# 685623_177_3.net
KiCad netlist of a schematic drawn in Altium Designer
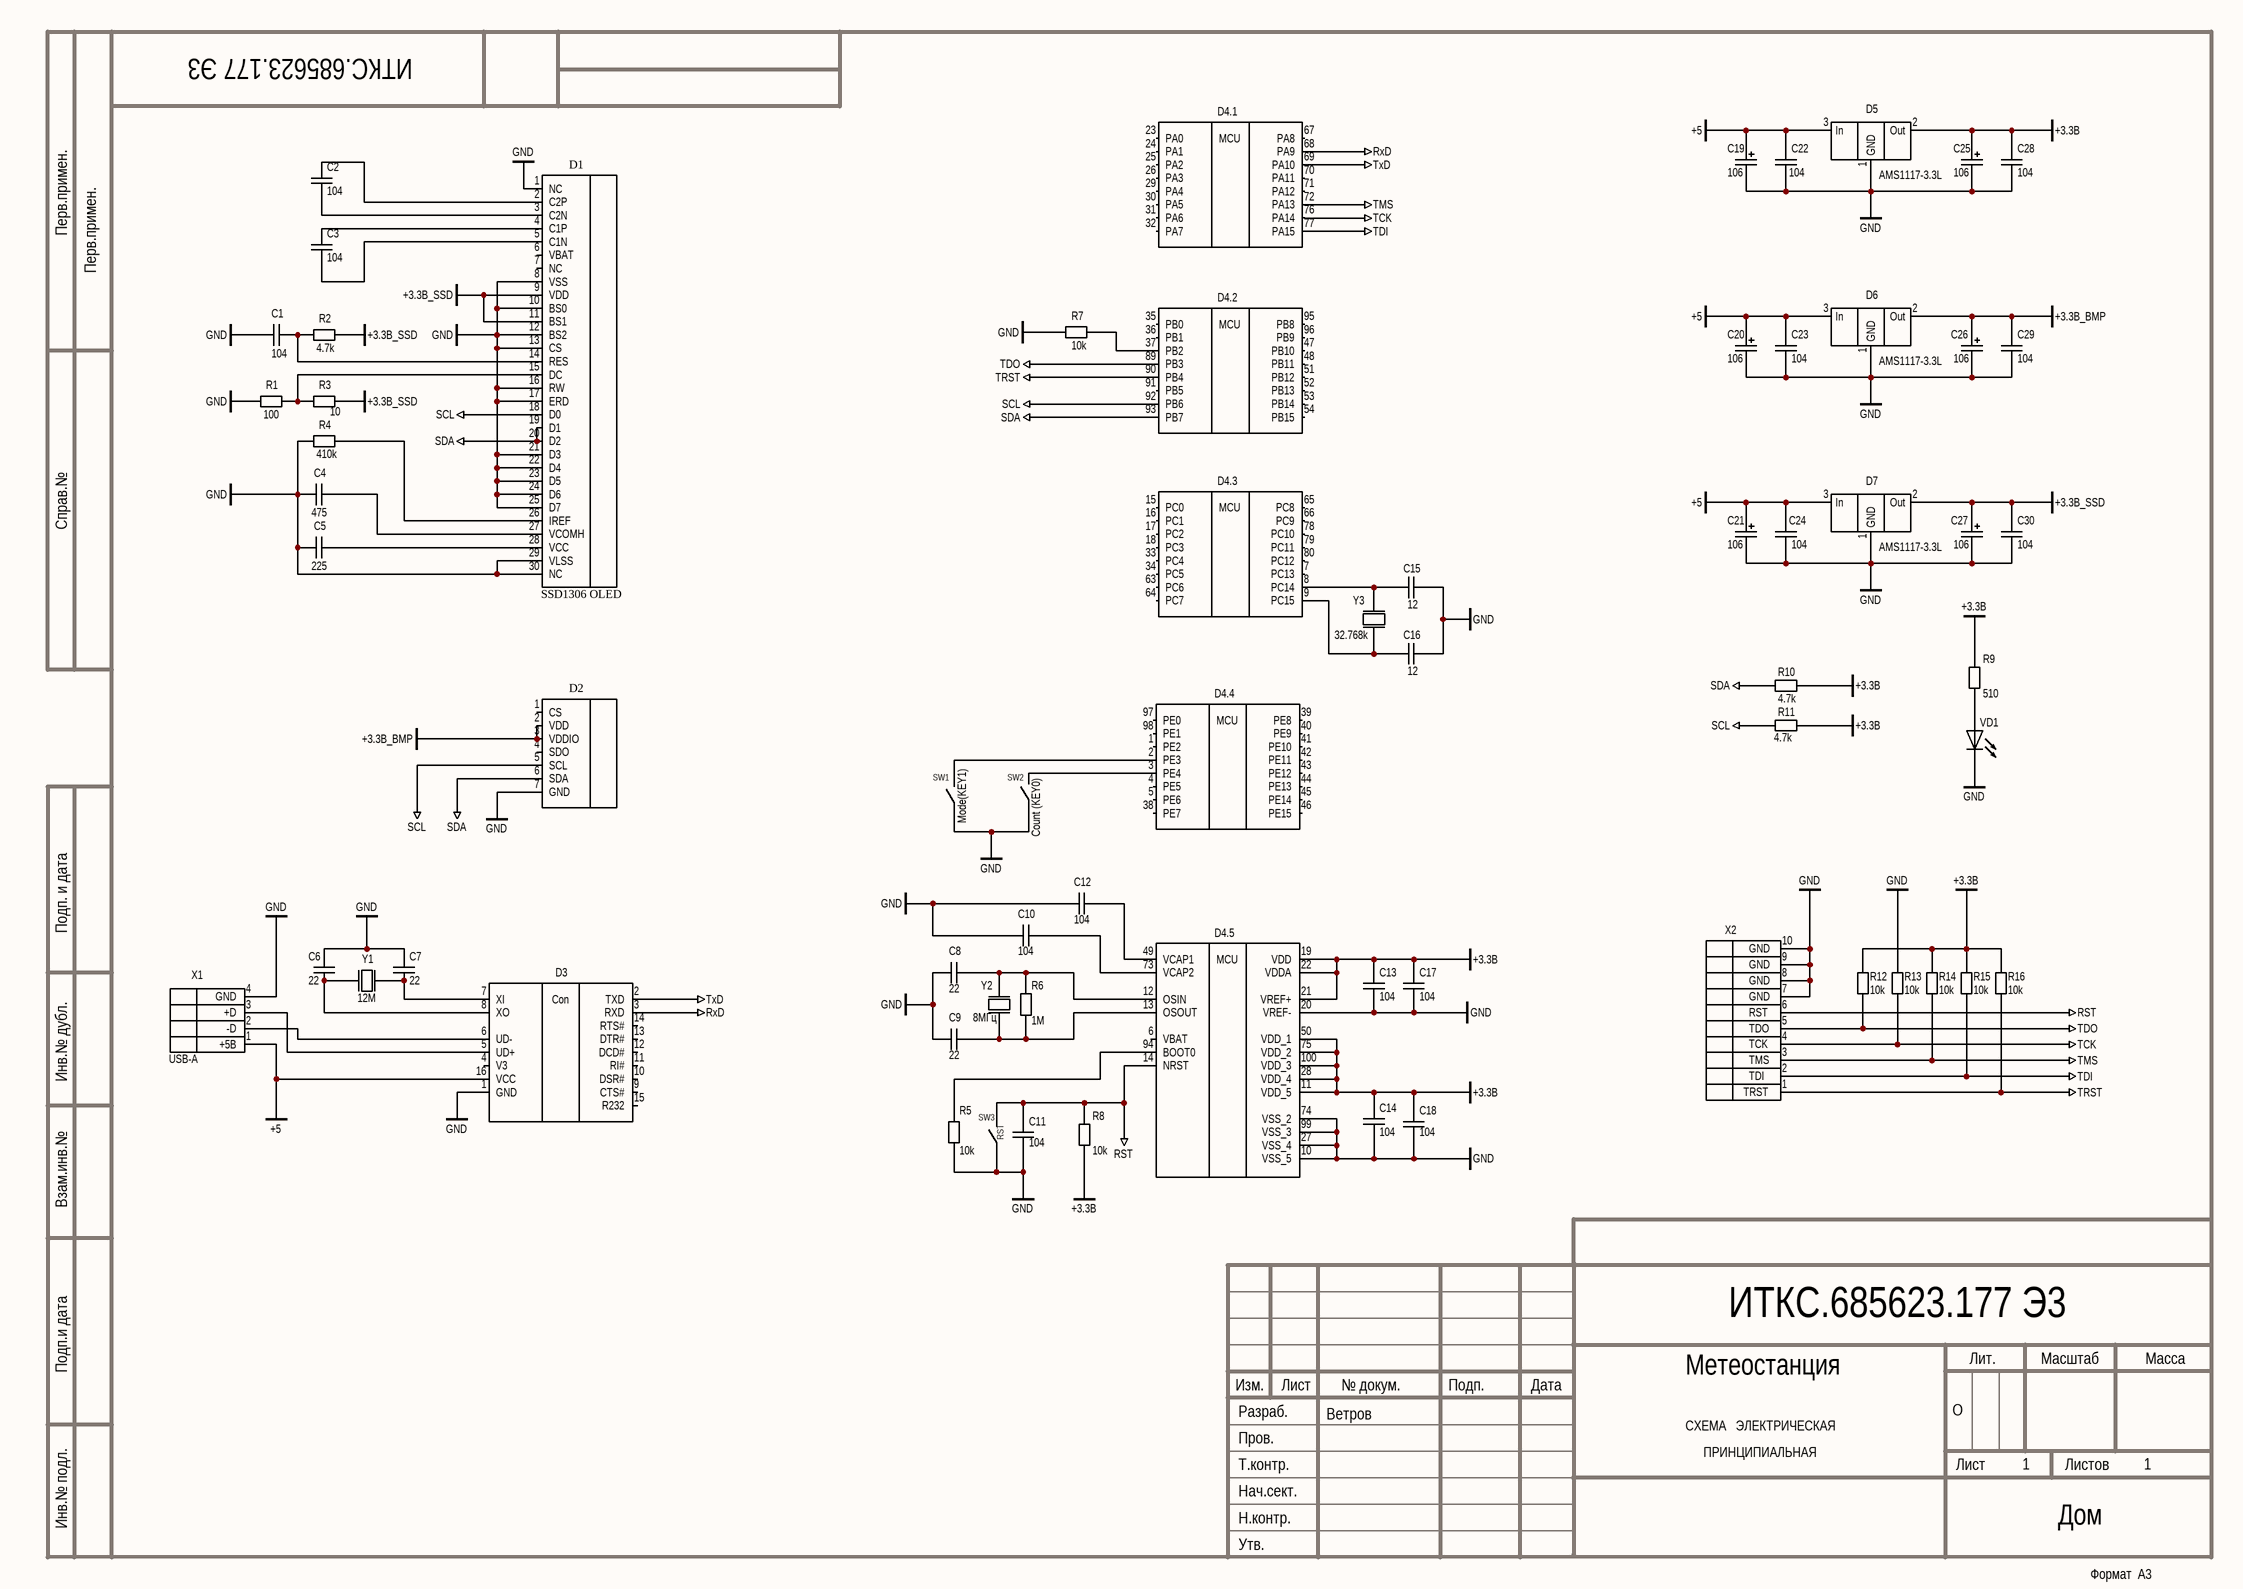
[diagram p0: ИТКС.685623.177 Э3.SchDoc]

(export (version "E")
  (design (tool "Eeschema 10.0.6"))
  (components
    (comp (ref "C1") (value "104") (footprint "0603") (libsource (lib "MainLib") (part "C")))
    (comp (ref "C2") (value "104") (footprint "0603") (libsource (lib "MainLib") (part "C")))
    (comp (ref "C3") (value "104") (footprint "0603") (libsource (lib "MainLib") (part "C")))
    (comp (ref "C4") (value "475") (footprint "0603") (libsource (lib "MainLib") (part "C")))
    (comp (ref "C5") (value "225") (footprint "0603") (libsource (lib "MainLib") (part "C")))
    (comp (ref "C6") (value "22") (footprint "0603") (libsource (lib "MainLib") (part "C")))
    (comp (ref "C7") (value "22") (footprint "0603") (libsource (lib "MainLib") (part "C")))
    (comp (ref "C8") (value "22") (footprint "0603") (libsource (lib "MainLib") (part "C")))
    (comp (ref "C9") (value "22") (footprint "0603") (libsource (lib "MainLib") (part "C")))
    (comp (ref "C10") (value "104") (footprint "0603") (libsource (lib "MainLib") (part "C")))
    (comp (ref "C11") (value "104") (footprint "0603") (libsource (lib "MainLib") (part "C")))
    (comp (ref "C12") (value "104") (footprint "0603") (libsource (lib "MainLib") (part "C")))
    (comp (ref "C13") (value "104") (footprint "0603") (libsource (lib "MainLib") (part "C")))
    (comp (ref "C14") (value "104") (footprint "0603") (libsource (lib "MainLib") (part "C")))
    (comp (ref "C15") (value "12") (footprint "0603") (libsource (lib "MainLib") (part "C")))
    (comp (ref "C16") (value "12") (footprint "0603") (libsource (lib "MainLib") (part "C")))
    (comp (ref "C17") (value "104") (footprint "0603") (libsource (lib "MainLib") (part "C")))
    (comp (ref "C18") (value "104") (footprint "0603") (libsource (lib "MainLib") (part "C")))
    (comp (ref "C19")
      (value "106")
      (footprint "EIA_6032–28")
      (description "TECAP EIA 6032–28")
      (libsource (lib "MainLib") (part "C+ TECAP"))
    )
    (comp (ref "C20")
      (value "106")
      (footprint "EIA_6032–28")
      (description "TECAP EIA 6032–28")
      (libsource (lib "MainLib") (part "C+ TECAP"))
    )
    (comp (ref "C21")
      (value "106")
      (footprint "EIA_6032–28")
      (description "TECAP EIA 6032–28")
      (libsource (lib "MainLib") (part "C+ TECAP"))
    )
    (comp (ref "C22") (value "104") (footprint "0603") (libsource (lib "MainLib") (part "C")))
    (comp (ref "C23") (value "104") (footprint "0603") (libsource (lib "MainLib") (part "C")))
    (comp (ref "C24") (value "104") (footprint "0603") (libsource (lib "MainLib") (part "C")))
    (comp (ref "C25")
      (value "106")
      (footprint "EIA_6032–28")
      (description "TECAP EIA 6032–28")
      (libsource (lib "MainLib") (part "C+ TECAP"))
    )
    (comp (ref "C26")
      (value "106")
      (footprint "EIA_6032–28")
      (description "TECAP EIA 6032–28")
      (libsource (lib "MainLib") (part "C+ TECAP"))
    )
    (comp (ref "C27")
      (value "106")
      (footprint "EIA_6032–28")
      (description "TECAP EIA 6032–28")
      (libsource (lib "MainLib") (part "C+ TECAP"))
    )
    (comp (ref "C28") (value "104") (footprint "0603") (libsource (lib "MainLib") (part "C")))
    (comp (ref "C29") (value "104") (footprint "0603") (libsource (lib "MainLib") (part "C")))
    (comp (ref "C30") (value "104") (footprint "0603") (libsource (lib "MainLib") (part "C")))
    (comp (ref "D1")
      (value "SSD1306 OLED")
      (footprint "SSD1306")
      (libsource (lib "MainLib") (part "SSD1306 OLED"))
    )
    (comp (ref "D2") (value "BMP180") (footprint "BMP180") (libsource (lib "MainLib") (part "BMP180")))
    (comp (ref "D3") (value "CH340G") (footprint "SOP16") (libsource (lib "MainLib") (part "CH340G")))
    (comp (ref "D4")
      (value "STM32F407VE")
      (footprint "LQFP100")
      (description "ARM3")
      (libsource (lib "MainLib") (part "STM32F407VE"))
    )
    (comp (ref "D5")
      (value "AMS1117-3.3L")
      (footprint "SOT223-4N")
      (libsource (lib "MainLib") (part "AMS1117-3.3L"))
    )
    (comp (ref "D6")
      (value "AMS1117-3.3L")
      (footprint "SOT223-4N")
      (libsource (lib "MainLib") (part "AMS1117-3.3L"))
    )
    (comp (ref "D7")
      (value "AMS1117-3.3L")
      (footprint "SOT223-4N")
      (libsource (lib "MainLib") (part "AMS1117-3.3L"))
    )
    (comp (ref "R1") (value "100") (footprint "0603") (libsource (lib "MainLib") (part "R")))
    (comp (ref "R2") (value "4.7k") (footprint "0603") (libsource (lib "MainLib") (part "R")))
    (comp (ref "R3") (value "10") (footprint "0603") (libsource (lib "MainLib") (part "R")))
    (comp (ref "R4") (value "410k") (footprint "0603") (libsource (lib "MainLib") (part "R")))
    (comp (ref "R5") (value "10k") (footprint "0603") (libsource (lib "MainLib") (part "R")))
    (comp (ref "R6") (value "1M") (footprint "0603") (libsource (lib "MainLib") (part "R")))
    (comp (ref "R7") (value "10k") (footprint "0603") (libsource (lib "MainLib") (part "R")))
    (comp (ref "R8") (value "10k") (footprint "0603") (libsource (lib "MainLib") (part "R")))
    (comp (ref "R9") (value "510") (footprint "0603") (libsource (lib "MainLib") (part "R")))
    (comp (ref "R10") (value "4.7k") (footprint "0603") (libsource (lib "MainLib") (part "R")))
    (comp (ref "R11") (value "4.7k") (footprint "0603") (libsource (lib "MainLib") (part "R")))
    (comp (ref "R12") (value "10k") (footprint "0603") (libsource (lib "MainLib") (part "R")))
    (comp (ref "R13") (value "10k") (footprint "0603") (libsource (lib "MainLib") (part "R")))
    (comp (ref "R14") (value "10k") (footprint "0603") (libsource (lib "MainLib") (part "R")))
    (comp (ref "R15") (value "10k") (footprint "0603") (libsource (lib "MainLib") (part "R")))
    (comp (ref "R16") (value "10k") (footprint "0603") (libsource (lib "MainLib") (part "R")))
    (comp (ref "SW1") (value "Mode(KEY1)") (footprint "0603") (libsource (lib "MainLib") (part "Button")))
    (comp (ref "SW2") (value "Count (KEY0)") (footprint "0603") (libsource (lib "MainLib") (part "Button")))
    (comp (ref "SW3") (value "RST") (footprint "0603") (libsource (lib "MainLib") (part "Button")))
    (comp (ref "VD1")
      (value "LED SMD 0805")
      (footprint "Led Diode 0805")
      (libsource (lib "MainLib") (part "LED SMD 0805"))
    )
    (comp (ref "X1")
      (value "USB-A")
      (footprint "USB-ASM (DS1098-B)")
      (libsource (lib "MainLib") (part "USB-A"))
    )
    (comp (ref "X2") (value "PLC-10") (footprint "PLC-10") (libsource (lib "MainLib") (part "PLC-10")))
    (comp (ref "Y1") (value "12M") (footprint "HC-49SM") (libsource (lib "MainLib") (part "BQ")))
    (comp (ref "Y2") (value "8МГц") (footprint "HC-49SM") (libsource (lib "MainLib") (part "BQ")))
    (comp (ref "Y3") (value "32.768k") (footprint "HC-49SM") (libsource (lib "MainLib") (part "BQ")))
  )
  (nets
    (net (code "1") (name "+3.3В") (class "Default")
      (node (ref "C13") (pin "1") (pinfunction "1_1") (pintype "passive"))
      (node (ref "C14") (pin "1") (pinfunction "1_1") (pintype "passive"))
      (node (ref "C17") (pin "1") (pinfunction "1_1") (pintype "passive"))
      (node (ref "C18") (pin "1") (pinfunction "1_1") (pintype "passive"))
      (node (ref "C25") (pin "1") (pinfunction "1_1") (pintype "passive"))
      (node (ref "C28") (pin "2") (pinfunction "2_2") (pintype "passive"))
      (node (ref "D4") (pin "100") (pinfunction "VDD_3_100") (pintype "passive"))
      (node (ref "D4") (pin "11") (pinfunction "VDD_5_11") (pintype "passive"))
      (node (ref "D4") (pin "19") (pinfunction "VDD_19") (pintype "passive"))
      (node (ref "D4") (pin "21") (pinfunction "VREF+_21") (pintype "passive"))
      (node (ref "D4") (pin "22") (pinfunction "VDDA_22") (pintype "passive"))
      (node (ref "D4") (pin "28") (pinfunction "VDD_4_28") (pintype "passive"))
      (node (ref "D4") (pin "50") (pinfunction "VDD_1_50") (pintype "passive"))
      (node (ref "D4") (pin "75") (pinfunction "VDD_2_75") (pintype "passive"))
      (node (ref "D5") (pin "2") (pinfunction "Out_2") (pintype "passive"))
      (node (ref "R10") (pin "2") (pinfunction "2_2") (pintype "passive"))
      (node (ref "R11") (pin "2") (pinfunction "2_2") (pintype "passive"))
      (node (ref "R12") (pin "2") (pinfunction "2_2") (pintype "passive"))
      (node (ref "R14") (pin "2") (pinfunction "2_2") (pintype "passive"))
      (node (ref "R15") (pin "2") (pinfunction "2_2") (pintype "passive"))
      (node (ref "R16") (pin "2") (pinfunction "2_2") (pintype "passive"))
      (node (ref "R8") (pin "2") (pinfunction "2_2") (pintype "passive"))
      (node (ref "R9") (pin "1") (pinfunction "1_1") (pintype "passive"))
    )
    (net (code "2") (name "+3.3В_BMP") (class "Default")
      (node (ref "C26") (pin "1") (pinfunction "1_1") (pintype "passive"))
      (node (ref "C29") (pin "2") (pinfunction "2_2") (pintype "passive"))
      (node (ref "D2") (pin "2") (pinfunction "VDD_2") (pintype "passive"))
      (node (ref "D2") (pin "3") (pinfunction "VDDIO_3") (pintype "passive"))
      (node (ref "D6") (pin "2") (pinfunction "Out_2") (pintype "passive"))
    )
    (net (code "3") (name "+3.3В_SSD") (class "Default")
      (node (ref "C27") (pin "1") (pinfunction "1_1") (pintype "passive"))
      (node (ref "C30") (pin "2") (pinfunction "2_2") (pintype "passive"))
      (node (ref "D1") (pin "11") (pinfunction "BS1_11") (pintype "passive"))
      (node (ref "D1") (pin "9") (pinfunction "VDD_9") (pintype "passive"))
      (node (ref "D7") (pin "2") (pinfunction "Out_2") (pintype "passive"))
      (node (ref "R2") (pin "1") (pinfunction "1_1") (pintype "passive"))
      (node (ref "R3") (pin "1") (pinfunction "1_1") (pintype "passive"))
    )
    (net (code "4") (name "+5") (class "Default")
      (node (ref "C19") (pin "1") (pinfunction "1_1") (pintype "passive"))
      (node (ref "C20") (pin "1") (pinfunction "1_1") (pintype "passive"))
      (node (ref "C21") (pin "1") (pinfunction "1_1") (pintype "passive"))
      (node (ref "C22") (pin "2") (pinfunction "2_2") (pintype "passive"))
      (node (ref "C23") (pin "2") (pinfunction "2_2") (pintype "passive"))
      (node (ref "C24") (pin "2") (pinfunction "2_2") (pintype "passive"))
      (node (ref "D3") (pin "16") (pinfunction "VCC_16") (pintype "passive"))
      (node (ref "D5") (pin "3") (pinfunction "In_3") (pintype "passive"))
      (node (ref "D6") (pin "3") (pinfunction "In_3") (pintype "passive"))
      (node (ref "D7") (pin "3") (pinfunction "In_3") (pintype "passive"))
      (node (ref "X1") (pin "1") (pinfunction "+5В_1") (pintype "passive"))
    )
    (net (code "5") (name "GND") (class "Default")
      (node (ref "C1") (pin "1") (pinfunction "1_1") (pintype "passive"))
      (node (ref "C10") (pin "2") (pinfunction "2_2") (pintype "passive"))
      (node (ref "C11") (pin "1") (pinfunction "1_1") (pintype "passive"))
      (node (ref "C12") (pin "2") (pinfunction "2_2") (pintype "passive"))
      (node (ref "C13") (pin "2") (pinfunction "2_2") (pintype "passive"))
      (node (ref "C14") (pin "2") (pinfunction "2_2") (pintype "passive"))
      (node (ref "C15") (pin "1") (pinfunction "1_1") (pintype "passive"))
      (node (ref "C16") (pin "1") (pinfunction "1_1") (pintype "passive"))
      (node (ref "C17") (pin "2") (pinfunction "2_2") (pintype "passive"))
      (node (ref "C18") (pin "2") (pinfunction "2_2") (pintype "passive"))
      (node (ref "C19") (pin "2") (pinfunction "2_2") (pintype "passive"))
      (node (ref "C20") (pin "2") (pinfunction "2_2") (pintype "passive"))
      (node (ref "C21") (pin "2") (pinfunction "2_2") (pintype "passive"))
      (node (ref "C22") (pin "1") (pinfunction "1_1") (pintype "passive"))
      (node (ref "C23") (pin "1") (pinfunction "1_1") (pintype "passive"))
      (node (ref "C24") (pin "1") (pinfunction "1_1") (pintype "passive"))
      (node (ref "C25") (pin "2") (pinfunction "2_2") (pintype "passive"))
      (node (ref "C26") (pin "2") (pinfunction "2_2") (pintype "passive"))
      (node (ref "C27") (pin "2") (pinfunction "2_2") (pintype "passive"))
      (node (ref "C28") (pin "1") (pinfunction "1_1") (pintype "passive"))
      (node (ref "C29") (pin "1") (pinfunction "1_1") (pintype "passive"))
      (node (ref "C30") (pin "1") (pinfunction "1_1") (pintype "passive"))
      (node (ref "C4") (pin "1") (pinfunction "1_1") (pintype "passive"))
      (node (ref "C5") (pin "1") (pinfunction "1_1") (pintype "passive"))
      (node (ref "C6") (pin "2") (pinfunction "2_2") (pintype "passive"))
      (node (ref "C7") (pin "2") (pinfunction "2_2") (pintype "passive"))
      (node (ref "C8") (pin "2") (pinfunction "2_2") (pintype "passive"))
      (node (ref "C9") (pin "2") (pinfunction "2_2") (pintype "passive"))
      (node (ref "D1") (pin "1") (pinfunction "NC_1") (pintype "passive"))
      (node (ref "D1") (pin "10") (pinfunction "BS0_10") (pintype "passive"))
      (node (ref "D1") (pin "12") (pinfunction "BS2_12") (pintype "passive"))
      (node (ref "D1") (pin "13") (pinfunction "CS_13") (pintype "passive"))
      (node (ref "D1") (pin "16") (pinfunction "RW_16") (pintype "passive"))
      (node (ref "D1") (pin "17") (pinfunction "ERD_17") (pintype "passive"))
      (node (ref "D1") (pin "21") (pinfunction "D3_21") (pintype "passive"))
      (node (ref "D1") (pin "22") (pinfunction "D4_22") (pintype "passive"))
      (node (ref "D1") (pin "23") (pinfunction "D5_23") (pintype "passive"))
      (node (ref "D1") (pin "24") (pinfunction "D6_24") (pintype "passive"))
      (node (ref "D1") (pin "25") (pinfunction "D7_25") (pintype "passive"))
      (node (ref "D1") (pin "29") (pinfunction "VLSS_29") (pintype "passive"))
      (node (ref "D1") (pin "30") (pinfunction "NC_30") (pintype "passive"))
      (node (ref "D1") (pin "8") (pinfunction "VSS_8") (pintype "passive"))
      (node (ref "D2") (pin "7") (pinfunction "GND_7") (pintype "passive"))
      (node (ref "D3") (pin "1") (pinfunction "GND_1") (pintype "passive"))
      (node (ref "D4") (pin "10") (pinfunction "VSS_5_10") (pintype "passive"))
      (node (ref "D4") (pin "20") (pinfunction "VREF-_20") (pintype "passive"))
      (node (ref "D4") (pin "27") (pinfunction "VSS_4_27") (pintype "passive"))
      (node (ref "D4") (pin "74") (pinfunction "VSS_2_74") (pintype "passive"))
      (node (ref "D4") (pin "99") (pinfunction "VSS_3_99") (pintype "passive"))
      (node (ref "D5") (pin "1") (pinfunction "GND_1") (pintype "passive"))
      (node (ref "D6") (pin "1") (pinfunction "GND_1") (pintype "passive"))
      (node (ref "D7") (pin "1") (pinfunction "GND_1") (pintype "passive"))
      (node (ref "R1") (pin "2") (pinfunction "2_2") (pintype "passive"))
      (node (ref "R13") (pin "2") (pinfunction "2_2") (pintype "passive"))
      (node (ref "R4") (pin "2") (pinfunction "2_2") (pintype "passive"))
      (node (ref "R5") (pin "2") (pinfunction "2_2") (pintype "passive"))
      (node (ref "R7") (pin "1") (pinfunction "1_1") (pintype "passive"))
      (node (ref "SW1") (pin "1") (pinfunction "1_1") (pintype "passive"))
      (node (ref "SW2") (pin "1") (pinfunction "1_1") (pintype "passive"))
      (node (ref "SW3") (pin "1") (pinfunction "1_1") (pintype "passive"))
      (node (ref "VD1") (pin "K") (pinfunction "K_K") (pintype "passive"))
      (node (ref "X1") (pin "4") (pinfunction "GND_4") (pintype "passive"))
      (node (ref "X2") (pin "10") (pintype "passive"))
      (node (ref "X2") (pin "7") (pintype "passive"))
      (node (ref "X2") (pin "8") (pintype "passive"))
      (node (ref "X2") (pin "9") (pintype "passive"))
    )
    (net (code "6") (name "Net-(D1-C1N)") (class "Default")
      (node (ref "C3") (pin "2") (pinfunction "2_2") (pintype "passive"))
      (node (ref "D1") (pin "5") (pinfunction "C1N_5") (pintype "passive"))
    )
    (net (code "7") (name "Net-(D1-C1P)") (class "Default")
      (node (ref "C3") (pin "1") (pinfunction "1_1") (pintype "passive"))
      (node (ref "D1") (pin "4") (pinfunction "C1P_4") (pintype "passive"))
    )
    (net (code "8") (name "Net-(D1-C2N)") (class "Default")
      (node (ref "C2") (pin "2") (pinfunction "2_2") (pintype "passive"))
      (node (ref "D1") (pin "3") (pinfunction "C2N_3") (pintype "passive"))
    )
    (net (code "9") (name "Net-(D1-C2P)") (class "Default")
      (node (ref "C2") (pin "1") (pinfunction "1_1") (pintype "passive"))
      (node (ref "D1") (pin "2") (pinfunction "C2P_2") (pintype "passive"))
    )
    (net (code "10") (name "Net-(D1-DC)") (class "Default")
      (node (ref "D1") (pin "15") (pinfunction "DC_15") (pintype "passive"))
      (node (ref "R1") (pin "1") (pinfunction "1_1") (pintype "passive"))
      (node (ref "R3") (pin "2") (pinfunction "2_2") (pintype "passive"))
    )
    (net (code "11") (name "Net-(D1-IREF)") (class "Default")
      (node (ref "D1") (pin "26") (pinfunction "IREF_26") (pintype "passive"))
      (node (ref "R4") (pin "1") (pinfunction "1_1") (pintype "passive"))
    )
    (net (code "12") (name "Net-(D1-RES)") (class "Default")
      (node (ref "C1") (pin "2") (pinfunction "2_2") (pintype "passive"))
      (node (ref "D1") (pin "14") (pinfunction "RES_14") (pintype "passive"))
      (node (ref "R2") (pin "2") (pinfunction "2_2") (pintype "passive"))
    )
    (net (code "13") (name "Net-(D1-VCC)") (class "Default")
      (node (ref "C5") (pin "2") (pinfunction "2_2") (pintype "passive"))
      (node (ref "D1") (pin "28") (pinfunction "VCC_28") (pintype "passive"))
    )
    (net (code "14") (name "Net-(D1-VCOMH)") (class "Default")
      (node (ref "C4") (pin "2") (pinfunction "2_2") (pintype "passive"))
      (node (ref "D1") (pin "27") (pinfunction "VCOMH_27") (pintype "passive"))
    )
    (net (code "15") (name "Net-(D3-UD+)") (class "Default")
      (node (ref "D3") (pin "5") (pinfunction "UD+_5") (pintype "passive"))
      (node (ref "X1") (pin "3") (pinfunction "+D_3") (pintype "passive"))
    )
    (net (code "16") (name "Net-(D3-UD-)") (class "Default")
      (node (ref "D3") (pin "6") (pinfunction "UD-_6") (pintype "passive"))
      (node (ref "X1") (pin "2") (pinfunction "-D_2") (pintype "passive"))
    )
    (net (code "17") (name "Net-(D3-XI)") (class "Default")
      (node (ref "C7") (pin "1") (pinfunction "1_1") (pintype "passive"))
      (node (ref "D3") (pin "7") (pinfunction "XI_7") (pintype "passive"))
      (node (ref "Y1") (pin "1") (pinfunction "1_1") (pintype "passive"))
    )
    (net (code "18") (name "Net-(D3-XO)") (class "Default")
      (node (ref "C6") (pin "1") (pinfunction "1_1") (pintype "passive"))
      (node (ref "D3") (pin "8") (pinfunction "XO_8") (pintype "passive"))
      (node (ref "Y1") (pin "2") (pinfunction "2_2") (pintype "passive"))
    )
    (net (code "19") (name "Net-(D4B-PB2)") (class "Default")
      (node (ref "D4") (pin "37") (pinfunction "PB2_37") (pintype "passive"))
      (node (ref "R7") (pin "2") (pinfunction "2_2") (pintype "passive"))
    )
    (net (code "20") (name "Net-(D4C-PC14)") (class "Default")
      (node (ref "C15") (pin "2") (pinfunction "2_2") (pintype "passive"))
      (node (ref "D4") (pin "8") (pinfunction "PC14_8") (pintype "passive"))
      (node (ref "Y3") (pin "2") (pinfunction "2_2") (pintype "passive"))
    )
    (net (code "21") (name "Net-(D4C-PC15)") (class "Default")
      (node (ref "C16") (pin "2") (pinfunction "2_2") (pintype "passive"))
      (node (ref "D4") (pin "9") (pinfunction "PC15_9") (pintype "passive"))
      (node (ref "Y3") (pin "1") (pinfunction "1_1") (pintype "passive"))
    )
    (net (code "22") (name "Net-(D4E-PE3)") (class "Default")
      (node (ref "D4") (pin "2") (pinfunction "PE3_2") (pintype "passive"))
      (node (ref "SW1") (pin "2") (pinfunction "2_2") (pintype "passive"))
    )
    (net (code "23") (name "Net-(D4E-PE4)") (class "Default")
      (node (ref "D4") (pin "3") (pinfunction "PE4_3") (pintype "passive"))
      (node (ref "SW2") (pin "2") (pinfunction "2_2") (pintype "passive"))
    )
    (net (code "24") (name "Net-(D4F-BOOT0)") (class "Default")
      (node (ref "D4") (pin "94") (pinfunction "BOOT0_94") (pintype "passive"))
      (node (ref "R5") (pin "1") (pinfunction "1_1") (pintype "passive"))
    )
    (net (code "25") (name "Net-(D4F-OSIN)") (class "Default")
      (node (ref "C8") (pin "1") (pinfunction "1_1") (pintype "passive"))
      (node (ref "D4") (pin "12") (pinfunction "OSIN_12") (pintype "passive"))
      (node (ref "R6") (pin "2") (pinfunction "2_2") (pintype "passive"))
      (node (ref "Y2") (pin "2") (pinfunction "2_2") (pintype "passive"))
    )
    (net (code "26") (name "Net-(D4F-OSOUT)") (class "Default")
      (node (ref "C9") (pin "1") (pinfunction "1_1") (pintype "passive"))
      (node (ref "D4") (pin "13") (pinfunction "OSOUT_13") (pintype "passive"))
      (node (ref "R6") (pin "1") (pinfunction "1_1") (pintype "passive"))
      (node (ref "Y2") (pin "1") (pinfunction "1_1") (pintype "passive"))
    )
    (net (code "27") (name "Net-(D4F-VCAP1)") (class "Default")
      (node (ref "C12") (pin "1") (pinfunction "1_1") (pintype "passive"))
      (node (ref "D4") (pin "49") (pinfunction "VCAP1_49") (pintype "passive"))
    )
    (net (code "28") (name "Net-(D4F-VCAP2)") (class "Default")
      (node (ref "C10") (pin "1") (pinfunction "1_1") (pintype "passive"))
      (node (ref "D4") (pin "73") (pinfunction "VCAP2_73") (pintype "passive"))
    )
    (net (code "29") (name "Net-(R9-Pad2)") (class "Default")
      (node (ref "R9") (pin "2") (pinfunction "2_2") (pintype "passive"))
      (node (ref "VD1") (pin "A") (pinfunction "A_A") (pintype "passive"))
    )
    (net (code "30") (name "RST") (class "Default")
      (node (ref "C11") (pin "2") (pinfunction "2_2") (pintype "passive"))
      (node (ref "D4") (pin "14") (pinfunction "NRST_14") (pintype "passive"))
      (node (ref "R8") (pin "1") (pinfunction "1_1") (pintype "passive"))
      (node (ref "SW3") (pin "2") (pinfunction "2_2") (pintype "passive"))
      (node (ref "X2") (pin "6") (pintype "passive"))
    )
    (net (code "31") (name "RxD") (class "Default")
      (node (ref "D3") (pin "3") (pinfunction "RXD_3") (pintype "passive"))
      (node (ref "D4") (pin "68") (pinfunction "PA9_68") (pintype "passive"))
    )
    (net (code "32") (name "SCL") (class "Default")
      (node (ref "D1") (pin "18") (pinfunction "D0_18") (pintype "passive"))
      (node (ref "D2") (pin "5") (pinfunction "SCL_5") (pintype "passive"))
      (node (ref "D4") (pin "92") (pinfunction "PB6_92") (pintype "passive"))
      (node (ref "R11") (pin "1") (pinfunction "1_1") (pintype "passive"))
    )
    (net (code "33") (name "SDA") (class "Default")
      (node (ref "D1") (pin "19") (pinfunction "D1_19") (pintype "passive"))
      (node (ref "D1") (pin "20") (pinfunction "D2_20") (pintype "passive"))
      (node (ref "D2") (pin "6") (pinfunction "SDA_6") (pintype "passive"))
      (node (ref "D4") (pin "93") (pinfunction "PB7_93") (pintype "passive"))
      (node (ref "R10") (pin "1") (pinfunction "1_1") (pintype "passive"))
    )
    (net (code "34") (name "TCK") (class "Default")
      (node (ref "D4") (pin "76") (pinfunction "PA14_76") (pintype "passive"))
      (node (ref "R13") (pin "1") (pinfunction "1_1") (pintype "passive"))
      (node (ref "X2") (pin "4") (pintype "passive"))
    )
    (net (code "35") (name "TDI") (class "Default")
      (node (ref "D4") (pin "77") (pinfunction "PA15_77") (pintype "passive"))
      (node (ref "R15") (pin "1") (pinfunction "1_1") (pintype "passive"))
      (node (ref "X2") (pin "2") (pintype "passive"))
    )
    (net (code "36") (name "TDO") (class "Default")
      (node (ref "D4") (pin "89") (pinfunction "PB3_89") (pintype "passive"))
      (node (ref "R12") (pin "1") (pinfunction "1_1") (pintype "passive"))
      (node (ref "X2") (pin "5") (pintype "passive"))
    )
    (net (code "37") (name "TMS") (class "Default")
      (node (ref "D4") (pin "72") (pinfunction "PA13_72") (pintype "passive"))
      (node (ref "R14") (pin "1") (pinfunction "1_1") (pintype "passive"))
      (node (ref "X2") (pin "3") (pintype "passive"))
    )
    (net (code "38") (name "TRST") (class "Default")
      (node (ref "D4") (pin "90") (pinfunction "PB4_90") (pintype "passive"))
      (node (ref "R16") (pin "1") (pinfunction "1_1") (pintype "passive"))
      (node (ref "X2") (pin "1") (pintype "passive"))
    )
    (net (code "39") (name "TxD") (class "Default")
      (node (ref "D3") (pin "2") (pinfunction "TXD_2") (pintype "passive"))
      (node (ref "D4") (pin "69") (pinfunction "PA10_69") (pintype "passive"))
    )
    (net (code "40") (name "unconnected-(D1-NC-Pad7)") (class "Default")
      (node (ref "D1") (pin "7") (pinfunction "NC_7") (pintype "passive"))
    )
    (net (code "41") (name "unconnected-(D1-VBAT-Pad6)") (class "Default")
      (node (ref "D1") (pin "6") (pinfunction "VBAT_6") (pintype "passive"))
    )
    (net (code "42") (name "unconnected-(D2-CS-Pad1)") (class "Default")
      (node (ref "D2") (pin "1") (pinfunction "CS_1") (pintype "passive"))
    )
    (net (code "43") (name "unconnected-(D2-SDO-Pad4)") (class "Default")
      (node (ref "D2") (pin "4") (pinfunction "SDO_4") (pintype "passive"))
    )
    (net (code "44") (name "unconnected-(D3-CTS#-Pad9)") (class "Default")
      (node (ref "D3") (pin "9") (pinfunction "CTS#_9") (pintype "passive"))
    )
    (net (code "45") (name "unconnected-(D3-DCD#-Pad12)") (class "Default")
      (node (ref "D3") (pin "12") (pinfunction "DCD#_12") (pintype "passive"))
    )
    (net (code "46") (name "unconnected-(D3-DSR#-Pad10)") (class "Default")
      (node (ref "D3") (pin "10") (pinfunction "DSR#_10") (pintype "passive"))
    )
    (net (code "47") (name "unconnected-(D3-DTR#-Pad13)") (class "Default")
      (node (ref "D3") (pin "13") (pinfunction "DTR#_13") (pintype "passive"))
    )
    (net (code "48") (name "unconnected-(D3-R232-Pad15)") (class "Default")
      (node (ref "D3") (pin "15") (pinfunction "R232_15") (pintype "passive"))
    )
    (net (code "49") (name "unconnected-(D3-RI#-Pad11)") (class "Default")
      (node (ref "D3") (pin "11") (pinfunction "RI#_11") (pintype "passive"))
    )
    (net (code "50") (name "unconnected-(D3-RTS#-Pad14)") (class "Default")
      (node (ref "D3") (pin "14") (pinfunction "RTS#_14") (pintype "passive"))
    )
    (net (code "51") (name "unconnected-(D3-V3-Pad4)") (class "Default")
      (node (ref "D3") (pin "4") (pinfunction "V3_4") (pintype "passive"))
    )
    (net (code "52") (name "unconnected-(D4A-PA0-Pad23)") (class "Default")
      (node (ref "D4") (pin "23") (pinfunction "PA0_23") (pintype "passive"))
    )
    (net (code "53") (name "unconnected-(D4A-PA1-Pad24)") (class "Default")
      (node (ref "D4") (pin "24") (pinfunction "PA1_24") (pintype "passive"))
    )
    (net (code "54") (name "unconnected-(D4A-PA2-Pad25)") (class "Default")
      (node (ref "D4") (pin "25") (pinfunction "PA2_25") (pintype "passive"))
    )
    (net (code "55") (name "unconnected-(D4A-PA3-Pad26)") (class "Default")
      (node (ref "D4") (pin "26") (pinfunction "PA3_26") (pintype "passive"))
    )
    (net (code "56") (name "unconnected-(D4A-PA4-Pad29)") (class "Default")
      (node (ref "D4") (pin "29") (pinfunction "PA4_29") (pintype "passive"))
    )
    (net (code "57") (name "unconnected-(D4A-PA5-Pad30)") (class "Default")
      (node (ref "D4") (pin "30") (pinfunction "PA5_30") (pintype "passive"))
    )
    (net (code "58") (name "unconnected-(D4A-PA6-Pad31)") (class "Default")
      (node (ref "D4") (pin "31") (pinfunction "PA6_31") (pintype "passive"))
    )
    (net (code "59") (name "unconnected-(D4A-PA7-Pad32)") (class "Default")
      (node (ref "D4") (pin "32") (pinfunction "PA7_32") (pintype "passive"))
    )
    (net (code "60") (name "unconnected-(D4A-PA8-Pad67)") (class "Default")
      (node (ref "D4") (pin "67") (pinfunction "PA8_67") (pintype "passive"))
    )
    (net (code "61") (name "unconnected-(D4A-PA11-Pad70)") (class "Default")
      (node (ref "D4") (pin "70") (pinfunction "PA11_70") (pintype "passive"))
    )
    (net (code "62") (name "unconnected-(D4A-PA12-Pad71)") (class "Default")
      (node (ref "D4") (pin "71") (pinfunction "PA12_71") (pintype "passive"))
    )
    (net (code "63") (name "unconnected-(D4B-PB0-Pad35)") (class "Default")
      (node (ref "D4") (pin "35") (pinfunction "PB0_35") (pintype "passive"))
    )
    (net (code "64") (name "unconnected-(D4B-PB1-Pad36)") (class "Default")
      (node (ref "D4") (pin "36") (pinfunction "PB1_36") (pintype "passive"))
    )
    (net (code "65") (name "unconnected-(D4B-PB5-Pad91)") (class "Default")
      (node (ref "D4") (pin "91") (pinfunction "PB5_91") (pintype "passive"))
    )
    (net (code "66") (name "unconnected-(D4B-PB8-Pad95)") (class "Default")
      (node (ref "D4") (pin "95") (pinfunction "PB8_95") (pintype "passive"))
    )
    (net (code "67") (name "unconnected-(D4B-PB9-Pad96)") (class "Default")
      (node (ref "D4") (pin "96") (pinfunction "PB9_96") (pintype "passive"))
    )
    (net (code "68") (name "unconnected-(D4B-PB10-Pad47)") (class "Default")
      (node (ref "D4") (pin "47") (pinfunction "PB10_47") (pintype "passive"))
    )
    (net (code "69") (name "unconnected-(D4B-PB11-Pad48)") (class "Default")
      (node (ref "D4") (pin "48") (pinfunction "PB11_48") (pintype "passive"))
    )
    (net (code "70") (name "unconnected-(D4B-PB12-Pad51)") (class "Default")
      (node (ref "D4") (pin "51") (pinfunction "PB12_51") (pintype "passive"))
    )
    (net (code "71") (name "unconnected-(D4B-PB13-Pad52)") (class "Default")
      (node (ref "D4") (pin "52") (pinfunction "PB13_52") (pintype "passive"))
    )
    (net (code "72") (name "unconnected-(D4B-PB14-Pad53)") (class "Default")
      (node (ref "D4") (pin "53") (pinfunction "PB14_53") (pintype "passive"))
    )
    (net (code "73") (name "unconnected-(D4B-PB15-Pad54)") (class "Default")
      (node (ref "D4") (pin "54") (pinfunction "PB15_54") (pintype "passive"))
    )
    (net (code "74") (name "unconnected-(D4C-PC0-Pad15)") (class "Default")
      (node (ref "D4") (pin "15") (pinfunction "PC0_15") (pintype "passive"))
    )
    (net (code "75") (name "unconnected-(D4C-PC1-Pad16)") (class "Default")
      (node (ref "D4") (pin "16") (pinfunction "PC1_16") (pintype "passive"))
    )
    (net (code "76") (name "unconnected-(D4C-PC2-Pad17)") (class "Default")
      (node (ref "D4") (pin "17") (pinfunction "PC2_17") (pintype "passive"))
    )
    (net (code "77") (name "unconnected-(D4C-PC3-Pad18)") (class "Default")
      (node (ref "D4") (pin "18") (pinfunction "PC3_18") (pintype "passive"))
    )
    (net (code "78") (name "unconnected-(D4C-PC4-Pad33)") (class "Default")
      (node (ref "D4") (pin "33") (pinfunction "PC4_33") (pintype "passive"))
    )
    (net (code "79") (name "unconnected-(D4C-PC5-Pad34)") (class "Default")
      (node (ref "D4") (pin "34") (pinfunction "PC5_34") (pintype "passive"))
    )
    (net (code "80") (name "unconnected-(D4C-PC6-Pad63)") (class "Default")
      (node (ref "D4") (pin "63") (pinfunction "PC6_63") (pintype "passive"))
    )
    (net (code "81") (name "unconnected-(D4C-PC7-Pad64)") (class "Default")
      (node (ref "D4") (pin "64") (pinfunction "PC7_64") (pintype "passive"))
    )
    (net (code "82") (name "unconnected-(D4C-PC8-Pad65)") (class "Default")
      (node (ref "D4") (pin "65") (pinfunction "PC8_65") (pintype "passive"))
    )
    (net (code "83") (name "unconnected-(D4C-PC9-Pad66)") (class "Default")
      (node (ref "D4") (pin "66") (pinfunction "PC9_66") (pintype "passive"))
    )
    (net (code "84") (name "unconnected-(D4C-PC10-Pad78)") (class "Default")
      (node (ref "D4") (pin "78") (pinfunction "PC10_78") (pintype "passive"))
    )
    (net (code "85") (name "unconnected-(D4C-PC11-Pad79)") (class "Default")
      (node (ref "D4") (pin "79") (pinfunction "PC11_79") (pintype "passive"))
    )
    (net (code "86") (name "unconnected-(D4C-PC12-Pad80)") (class "Default")
      (node (ref "D4") (pin "80") (pinfunction "PC12_80") (pintype "passive"))
    )
    (net (code "87") (name "unconnected-(D4C-PC13-Pad7)") (class "Default")
      (node (ref "D4") (pin "7") (pinfunction "PC13_7") (pintype "passive"))
    )
    (net (code "88") (name "unconnected-(D4E-PE0-Pad97)") (class "Default")
      (node (ref "D4") (pin "97") (pinfunction "PE0_97") (pintype "passive"))
    )
    (net (code "89") (name "unconnected-(D4E-PE1-Pad98)") (class "Default")
      (node (ref "D4") (pin "98") (pinfunction "PE1_98") (pintype "passive"))
    )
    (net (code "90") (name "unconnected-(D4E-PE2-Pad1)") (class "Default")
      (node (ref "D4") (pin "1") (pinfunction "PE2_1") (pintype "passive"))
    )
    (net (code "91") (name "unconnected-(D4E-PE5-Pad4)") (class "Default")
      (node (ref "D4") (pin "4") (pinfunction "PE5_4") (pintype "passive"))
    )
    (net (code "92") (name "unconnected-(D4E-PE6-Pad5)") (class "Default")
      (node (ref "D4") (pin "5") (pinfunction "PE6_5") (pintype "passive"))
    )
    (net (code "93") (name "unconnected-(D4E-PE7-Pad38)") (class "Default")
      (node (ref "D4") (pin "38") (pinfunction "PE7_38") (pintype "passive"))
    )
    (net (code "94") (name "unconnected-(D4E-PE8-Pad39)") (class "Default")
      (node (ref "D4") (pin "39") (pinfunction "PE8_39") (pintype "passive"))
    )
    (net (code "95") (name "unconnected-(D4E-PE9-Pad40)") (class "Default")
      (node (ref "D4") (pin "40") (pinfunction "PE9_40") (pintype "passive"))
    )
    (net (code "96") (name "unconnected-(D4E-PE10-Pad41)") (class "Default")
      (node (ref "D4") (pin "41") (pinfunction "PE10_41") (pintype "passive"))
    )
    (net (code "97") (name "unconnected-(D4E-PE11-Pad42)") (class "Default")
      (node (ref "D4") (pin "42") (pinfunction "PE11_42") (pintype "passive"))
    )
    (net (code "98") (name "unconnected-(D4E-PE12-Pad43)") (class "Default")
      (node (ref "D4") (pin "43") (pinfunction "PE12_43") (pintype "passive"))
    )
    (net (code "99") (name "unconnected-(D4E-PE13-Pad44)") (class "Default")
      (node (ref "D4") (pin "44") (pinfunction "PE13_44") (pintype "passive"))
    )
    (net (code "100") (name "unconnected-(D4E-PE14-Pad45)") (class "Default")
      (node (ref "D4") (pin "45") (pinfunction "PE14_45") (pintype "passive"))
    )
    (net (code "101") (name "unconnected-(D4E-PE15-Pad46)") (class "Default")
      (node (ref "D4") (pin "46") (pinfunction "PE15_46") (pintype "passive"))
    )
    (net (code "102") (name "unconnected-(D4F-VBAT-Pad6)") (class "Default")
      (node (ref "D4") (pin "6") (pinfunction "VBAT_6") (pintype "passive"))
    )
  )
)
